# source_eagle.net
KiCad netlist of a schematic drawn in EAGLE
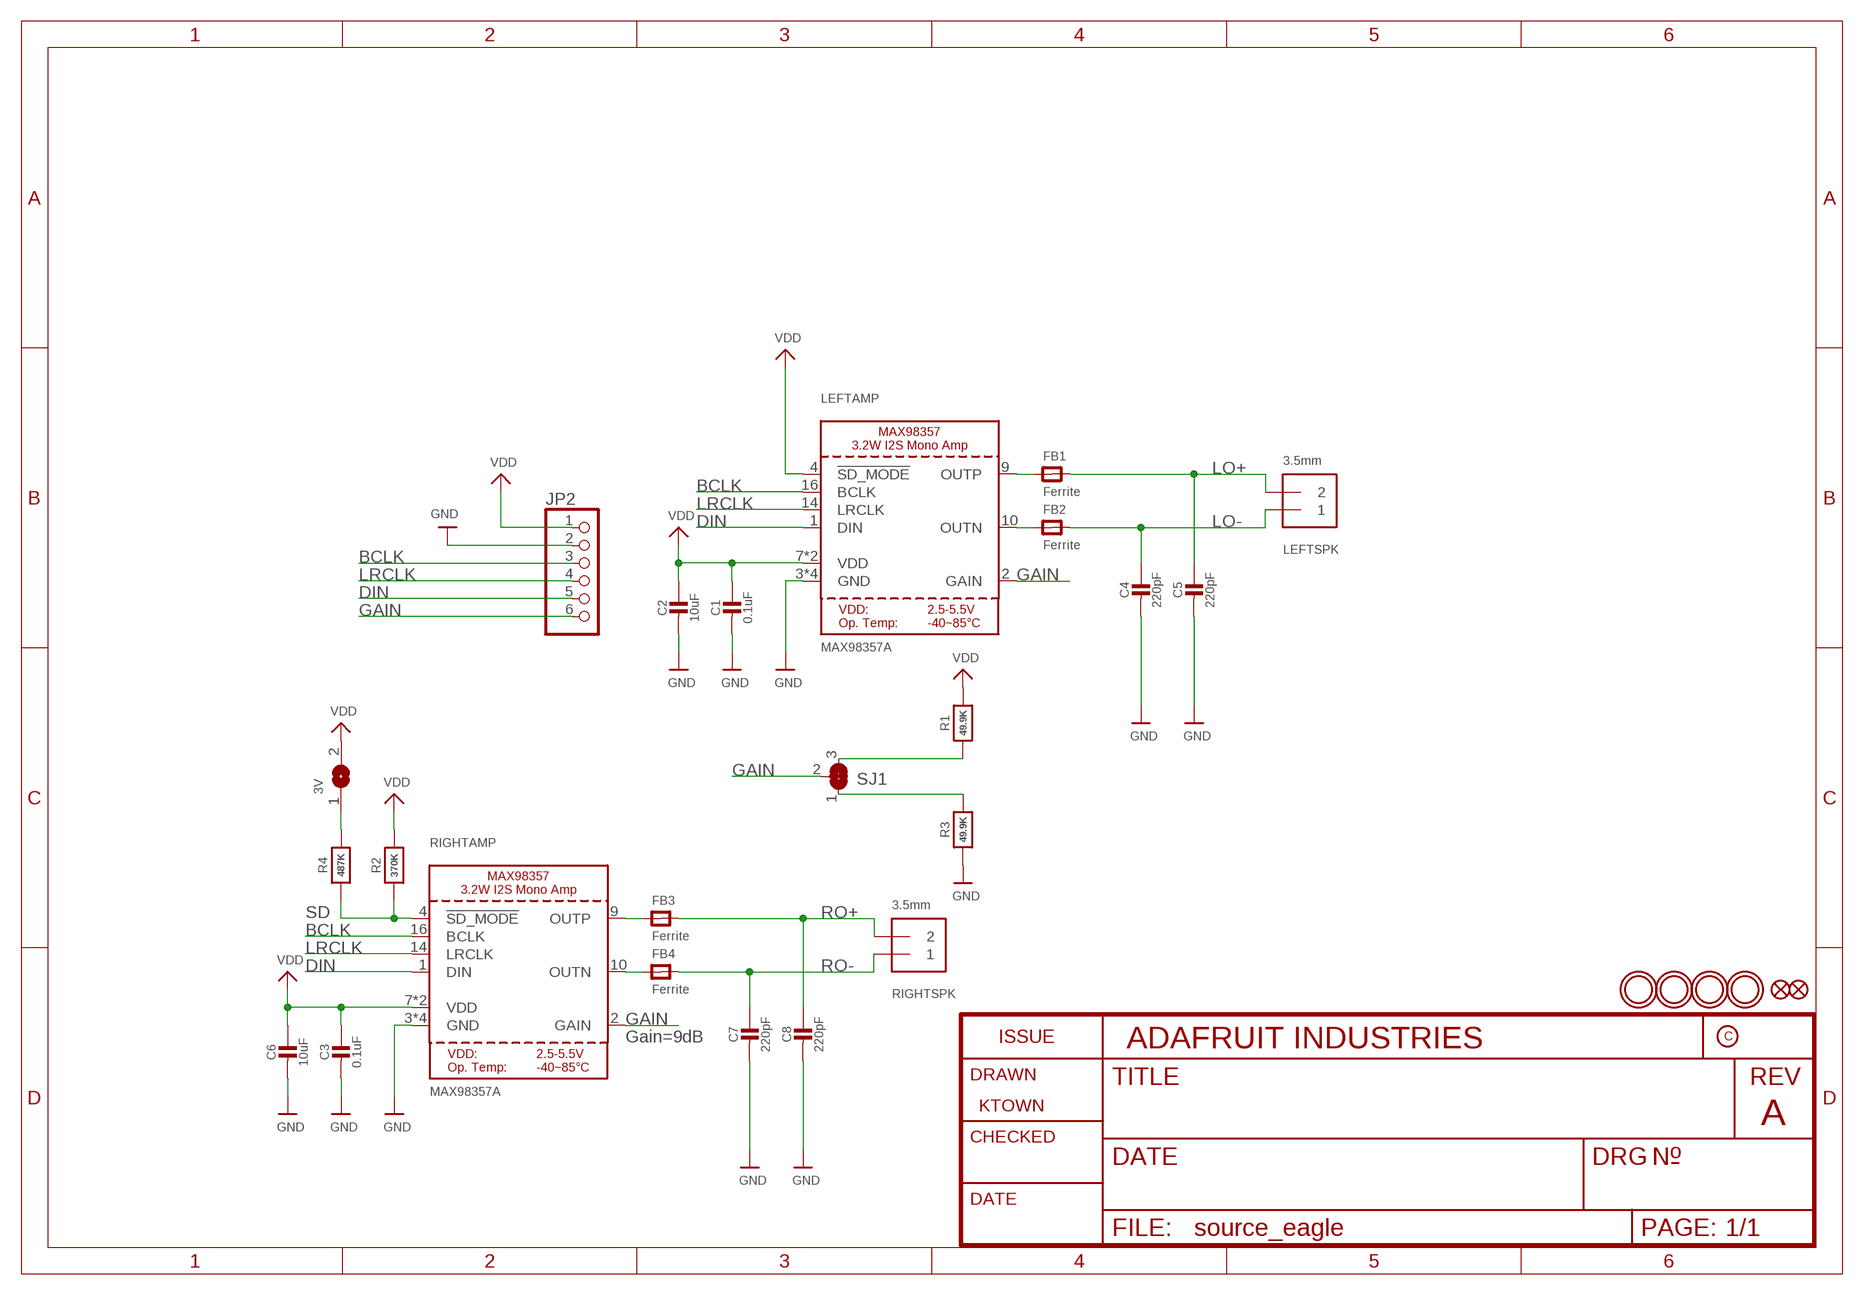
[diagram p0: schematic, sheet 1]

(export (version "E")
  (design (tool "Eeschema 10.0.6"))
  (components
    (comp (ref "3V")
      (value "SOLDERJUMPER")
      (footprint "eagle-import:SOLDERJUMPER_ARROW_NOPASTE")
      (libsource (lib "eagle-import") (part "SOLDERJUMPER"))
    )
    (comp (ref "C1")
      (value "0.1uF")
      (footprint "eagle-import:0603-NO")
      (libsource (lib "eagle-import") (part "CAP_CERAMIC0603_NO"))
    )
    (comp (ref "C2")
      (value "10uF")
      (footprint "eagle-import:0805-NO")
      (libsource (lib "eagle-import") (part "CAP_CERAMIC0805-NOOUTLINE"))
    )
    (comp (ref "C3")
      (value "0.1uF")
      (footprint "eagle-import:0603-NO")
      (libsource (lib "eagle-import") (part "CAP_CERAMIC0603_NO"))
    )
    (comp (ref "C4")
      (value "220pF")
      (footprint "eagle-import:0603-NO")
      (libsource (lib "eagle-import") (part "CAP_CERAMIC0603_NO"))
    )
    (comp (ref "C5")
      (value "220pF")
      (footprint "eagle-import:0603-NO")
      (libsource (lib "eagle-import") (part "CAP_CERAMIC0603_NO"))
    )
    (comp (ref "C6")
      (value "10uF")
      (footprint "eagle-import:0805-NO")
      (libsource (lib "eagle-import") (part "CAP_CERAMIC0805-NOOUTLINE"))
    )
    (comp (ref "C7")
      (value "220pF")
      (footprint "eagle-import:0603-NO")
      (libsource (lib "eagle-import") (part "CAP_CERAMIC0603_NO"))
    )
    (comp (ref "C8")
      (value "220pF")
      (footprint "eagle-import:0603-NO")
      (libsource (lib "eagle-import") (part "CAP_CERAMIC0603_NO"))
    )
    (comp (ref "FB1")
      (value "Ferrite")
      (footprint "eagle-import:0603-NO")
      (libsource (lib "eagle-import") (part "FERRITE-0603NO"))
    )
    (comp (ref "FB2")
      (value "Ferrite")
      (footprint "eagle-import:0603-NO")
      (libsource (lib "eagle-import") (part "FERRITE-0603NO"))
    )
    (comp (ref "FB3")
      (value "Ferrite")
      (footprint "eagle-import:0603-NO")
      (libsource (lib "eagle-import") (part "FERRITE-0603NO"))
    )
    (comp (ref "FB4")
      (value "Ferrite")
      (footprint "eagle-import:0603-NO")
      (libsource (lib "eagle-import") (part "FERRITE-0603NO"))
    )
    (comp (ref "FID1")
      (value "FIDUCIAL_0.5MM")
      (footprint "eagle-import:FIDUCIAL_0.5MM")
      (libsource (lib "eagle-import") (part "FIDUCIAL_0.5MM"))
    )
    (comp (ref "FID2")
      (value "FIDUCIAL_0.5MM")
      (footprint "eagle-import:FIDUCIAL_0.5MM")
      (libsource (lib "eagle-import") (part "FIDUCIAL_0.5MM"))
    )
    (comp (ref "JP2")
      (value "HEADER-1X670MIL")
      (footprint "eagle-import:1X06_ROUND_70")
      (libsource (lib "eagle-import") (part "HEADER-1X670MIL"))
    )
    (comp (ref "LEFTAMP")
      (value "MAX98357A")
      (footprint "eagle-import:QFN16_3MM")
      (libsource (lib "eagle-import") (part "AUDIOAMP_MAX98357"))
    )
    (comp (ref "LEFTSPK")
      (value "3.5mm")
      (footprint "eagle-import:TERMBLOCK_1X2-3.5MM")
      (libsource (lib "eagle-import") (part "TERMBLOCK_1X2_3.5MM"))
    )
    (comp (ref "R1")
      (value "49.9K")
      (footprint "eagle-import:0603-NO")
      (libsource (lib "eagle-import") (part "RESISTOR_0603_NOOUT"))
    )
    (comp (ref "R2")
      (value "370K")
      (footprint "eagle-import:0603-NO")
      (libsource (lib "eagle-import") (part "RESISTOR_0603_NOOUT"))
    )
    (comp (ref "R3")
      (value "49.9K")
      (footprint "eagle-import:0603-NO")
      (libsource (lib "eagle-import") (part "RESISTOR_0603_NOOUT"))
    )
    (comp (ref "R4")
      (value "487K")
      (footprint "eagle-import:0603-NO")
      (libsource (lib "eagle-import") (part "RESISTOR_0603_NOOUT"))
    )
    (comp (ref "RIGHTAMP")
      (value "MAX98357A")
      (footprint "eagle-import:QFN16_3MM")
      (libsource (lib "eagle-import") (part "AUDIOAMP_MAX98357"))
    )
    (comp (ref "RIGHTSPK")
      (value "3.5mm")
      (footprint "eagle-import:TERMBLOCK_1X2-3.5MM")
      (libsource (lib "eagle-import") (part "TERMBLOCK_1X2_3.5MM"))
    )
    (comp (ref "SJ1")
      (value "SOLDERJUMPER_2WAY")
      (footprint "eagle-import:SOLDERJUMPER_2WAY_OPEN_NOPASTE")
      (libsource (lib "eagle-import") (part "SOLDERJUMPER_2WAY"))
    )
    (comp (ref "U$9")
      (value "MOUNTINGHOLE2.5")
      (footprint "eagle-import:MOUNTINGHOLE_2.5_PLATED")
      (libsource (lib "eagle-import") (part "MOUNTINGHOLE2.5"))
    )
    (comp (ref "U$10")
      (value "MOUNTINGHOLE2.5")
      (footprint "eagle-import:MOUNTINGHOLE_2.5_PLATED")
      (libsource (lib "eagle-import") (part "MOUNTINGHOLE2.5"))
    )
    (comp (ref "U$23")
      (value "MOUNTINGHOLE2.5")
      (footprint "eagle-import:MOUNTINGHOLE_2.5_PLATED")
      (libsource (lib "eagle-import") (part "MOUNTINGHOLE2.5"))
    )
    (comp (ref "U$24")
      (value "MOUNTINGHOLE2.5")
      (footprint "eagle-import:MOUNTINGHOLE_2.5_PLATED")
      (libsource (lib "eagle-import") (part "MOUNTINGHOLE2.5"))
    )
  )
  (nets
    (net (code "1") (name "/BCLK") (class "Default")
      (node (ref "JP2") (pin "3") (pinfunction "3_3") (pintype "passive"))
      (node (ref "LEFTAMP") (pin "16") (pinfunction "BCLK_16") (pintype "bidirectional"))
      (node (ref "RIGHTAMP") (pin "16") (pinfunction "BCLK_16") (pintype "bidirectional"))
    )
    (net (code "2") (name "/DIN") (class "Default")
      (node (ref "JP2") (pin "5") (pinfunction "5_5") (pintype "passive"))
      (node (ref "LEFTAMP") (pin "1") (pinfunction "DIN_1") (pintype "bidirectional"))
      (node (ref "RIGHTAMP") (pin "1") (pinfunction "DIN_1") (pintype "bidirectional"))
    )
    (net (code "3") (name "/GAIN") (class "Default")
      (node (ref "JP2") (pin "6") (pinfunction "6_6") (pintype "passive"))
      (node (ref "LEFTAMP") (pin "2") (pinfunction "GAIN_2") (pintype "bidirectional"))
      (node (ref "RIGHTAMP") (pin "2") (pinfunction "GAIN_2") (pintype "bidirectional"))
      (node (ref "SJ1") (pin "2") (pinfunction "2_2") (pintype "passive"))
    )
    (net (code "4") (name "/LO+") (class "Default")
      (node (ref "C5") (pin "1") (pinfunction "1_1") (pintype "passive"))
      (node (ref "FB1") (pin "2") (pinfunction "P$2_2") (pintype "passive"))
      (node (ref "LEFTSPK") (pin "2") (pinfunction "2_2") (pintype "passive"))
    )
    (net (code "5") (name "/LO-") (class "Default")
      (node (ref "C4") (pin "1") (pinfunction "1_1") (pintype "passive"))
      (node (ref "FB2") (pin "2") (pinfunction "P$2_2") (pintype "passive"))
      (node (ref "LEFTSPK") (pin "1") (pinfunction "1_1") (pintype "passive"))
    )
    (net (code "6") (name "/LRCLK") (class "Default")
      (node (ref "JP2") (pin "4") (pinfunction "4_4") (pintype "passive"))
      (node (ref "LEFTAMP") (pin "14") (pinfunction "LRCLK_14") (pintype "bidirectional"))
      (node (ref "RIGHTAMP") (pin "14") (pinfunction "LRCLK_14") (pintype "bidirectional"))
    )
    (net (code "7") (name "/RO+") (class "Default")
      (node (ref "C8") (pin "1") (pinfunction "1_1") (pintype "passive"))
      (node (ref "FB3") (pin "2") (pinfunction "P$2_2") (pintype "passive"))
      (node (ref "RIGHTSPK") (pin "2") (pinfunction "2_2") (pintype "passive"))
    )
    (net (code "8") (name "/RO-") (class "Default")
      (node (ref "C7") (pin "1") (pinfunction "1_1") (pintype "passive"))
      (node (ref "FB4") (pin "2") (pinfunction "P$2_2") (pintype "passive"))
      (node (ref "RIGHTSPK") (pin "1") (pinfunction "1_1") (pintype "passive"))
    )
    (net (code "9") (name "/SD") (class "Default")
      (node (ref "R2") (pin "1") (pinfunction "1_1") (pintype "passive"))
      (node (ref "R4") (pin "1") (pinfunction "1_1") (pintype "passive"))
      (node (ref "RIGHTAMP") (pin "4") (pinfunction "~{SD_MODE}_4") (pintype "bidirectional"))
    )
    (net (code "10") (name "GND") (class "Default")
      (node (ref "C1") (pin "2") (pinfunction "2_2") (pintype "passive"))
      (node (ref "C2") (pin "2") (pinfunction "2_2") (pintype "passive"))
      (node (ref "C3") (pin "2") (pinfunction "2_2") (pintype "passive"))
      (node (ref "C4") (pin "2") (pinfunction "2_2") (pintype "passive"))
      (node (ref "C5") (pin "2") (pinfunction "2_2") (pintype "passive"))
      (node (ref "C6") (pin "2") (pinfunction "2_2") (pintype "passive"))
      (node (ref "C7") (pin "2") (pinfunction "2_2") (pintype "passive"))
      (node (ref "C8") (pin "2") (pinfunction "2_2") (pintype "passive"))
      (node (ref "JP2") (pin "2") (pinfunction "2_2") (pintype "passive"))
      (node (ref "LEFTAMP") (pin "11") (pinfunction "GND_11") (pintype "power_in"))
      (node (ref "LEFTAMP") (pin "15") (pinfunction "GND_15") (pintype "power_in"))
      (node (ref "LEFTAMP") (pin "3") (pinfunction "GND_3") (pintype "power_in"))
      (node (ref "LEFTAMP") (pin "THERMAL") (pinfunction "GND_THERMAL") (pintype "power_in"))
      (node (ref "R3") (pin "1") (pinfunction "1_1") (pintype "passive"))
      (node (ref "RIGHTAMP") (pin "11") (pinfunction "GND_11") (pintype "power_in"))
      (node (ref "RIGHTAMP") (pin "15") (pinfunction "GND_15") (pintype "power_in"))
      (node (ref "RIGHTAMP") (pin "3") (pinfunction "GND_3") (pintype "power_in"))
      (node (ref "RIGHTAMP") (pin "THERMAL") (pinfunction "GND_THERMAL") (pintype "power_in"))
    )
    (net (code "11") (name "Net-(3V-Pad1)") (class "Default")
      (node (ref "3V") (pin "1") (pinfunction "1_1") (pintype "passive"))
      (node (ref "R4") (pin "2") (pinfunction "2_2") (pintype "passive"))
    )
    (net (code "12") (name "Net-(FB1-P$1)") (class "Default")
      (node (ref "FB1") (pin "1") (pinfunction "P$1_1") (pintype "passive"))
      (node (ref "LEFTAMP") (pin "9") (pinfunction "OUTP_9") (pintype "output"))
    )
    (net (code "13") (name "Net-(FB2-P$1)") (class "Default")
      (node (ref "FB2") (pin "1") (pinfunction "P$1_1") (pintype "passive"))
      (node (ref "LEFTAMP") (pin "10") (pinfunction "OUTN_10") (pintype "output"))
    )
    (net (code "14") (name "Net-(FB3-P$1)") (class "Default")
      (node (ref "FB3") (pin "1") (pinfunction "P$1_1") (pintype "passive"))
      (node (ref "RIGHTAMP") (pin "9") (pinfunction "OUTP_9") (pintype "output"))
    )
    (net (code "15") (name "Net-(FB4-P$1)") (class "Default")
      (node (ref "FB4") (pin "1") (pinfunction "P$1_1") (pintype "passive"))
      (node (ref "RIGHTAMP") (pin "10") (pinfunction "OUTN_10") (pintype "output"))
    )
    (net (code "16") (name "Net-(R1-Pad1)") (class "Default")
      (node (ref "R1") (pin "1") (pinfunction "1_1") (pintype "passive"))
      (node (ref "SJ1") (pin "3") (pinfunction "3_3") (pintype "passive"))
    )
    (net (code "17") (name "Net-(R3-Pad2)") (class "Default")
      (node (ref "R3") (pin "2") (pinfunction "2_2") (pintype "passive"))
      (node (ref "SJ1") (pin "1") (pinfunction "1_1") (pintype "passive"))
    )
    (net (code "18") (name "VDD") (class "Default")
      (node (ref "3V") (pin "2") (pinfunction "2_2") (pintype "passive"))
      (node (ref "C1") (pin "1") (pinfunction "1_1") (pintype "passive"))
      (node (ref "C2") (pin "1") (pinfunction "1_1") (pintype "passive"))
      (node (ref "C3") (pin "1") (pinfunction "1_1") (pintype "passive"))
      (node (ref "C6") (pin "1") (pinfunction "1_1") (pintype "passive"))
      (node (ref "JP2") (pin "1") (pinfunction "1_1") (pintype "passive"))
      (node (ref "LEFTAMP") (pin "4") (pinfunction "~{SD_MODE}_4") (pintype "bidirectional"))
      (node (ref "LEFTAMP") (pin "7") (pinfunction "VDD_7") (pintype "power_in"))
      (node (ref "LEFTAMP") (pin "8") (pinfunction "VDD_8") (pintype "power_in"))
      (node (ref "R1") (pin "2") (pinfunction "2_2") (pintype "passive"))
      (node (ref "R2") (pin "2") (pinfunction "2_2") (pintype "passive"))
      (node (ref "RIGHTAMP") (pin "7") (pinfunction "VDD_7") (pintype "power_in"))
      (node (ref "RIGHTAMP") (pin "8") (pinfunction "VDD_8") (pintype "power_in"))
    )
  )
)
